# Elecrow_SIMduino_v2_2.net
KiCad netlist of a schematic drawn in EAGLE
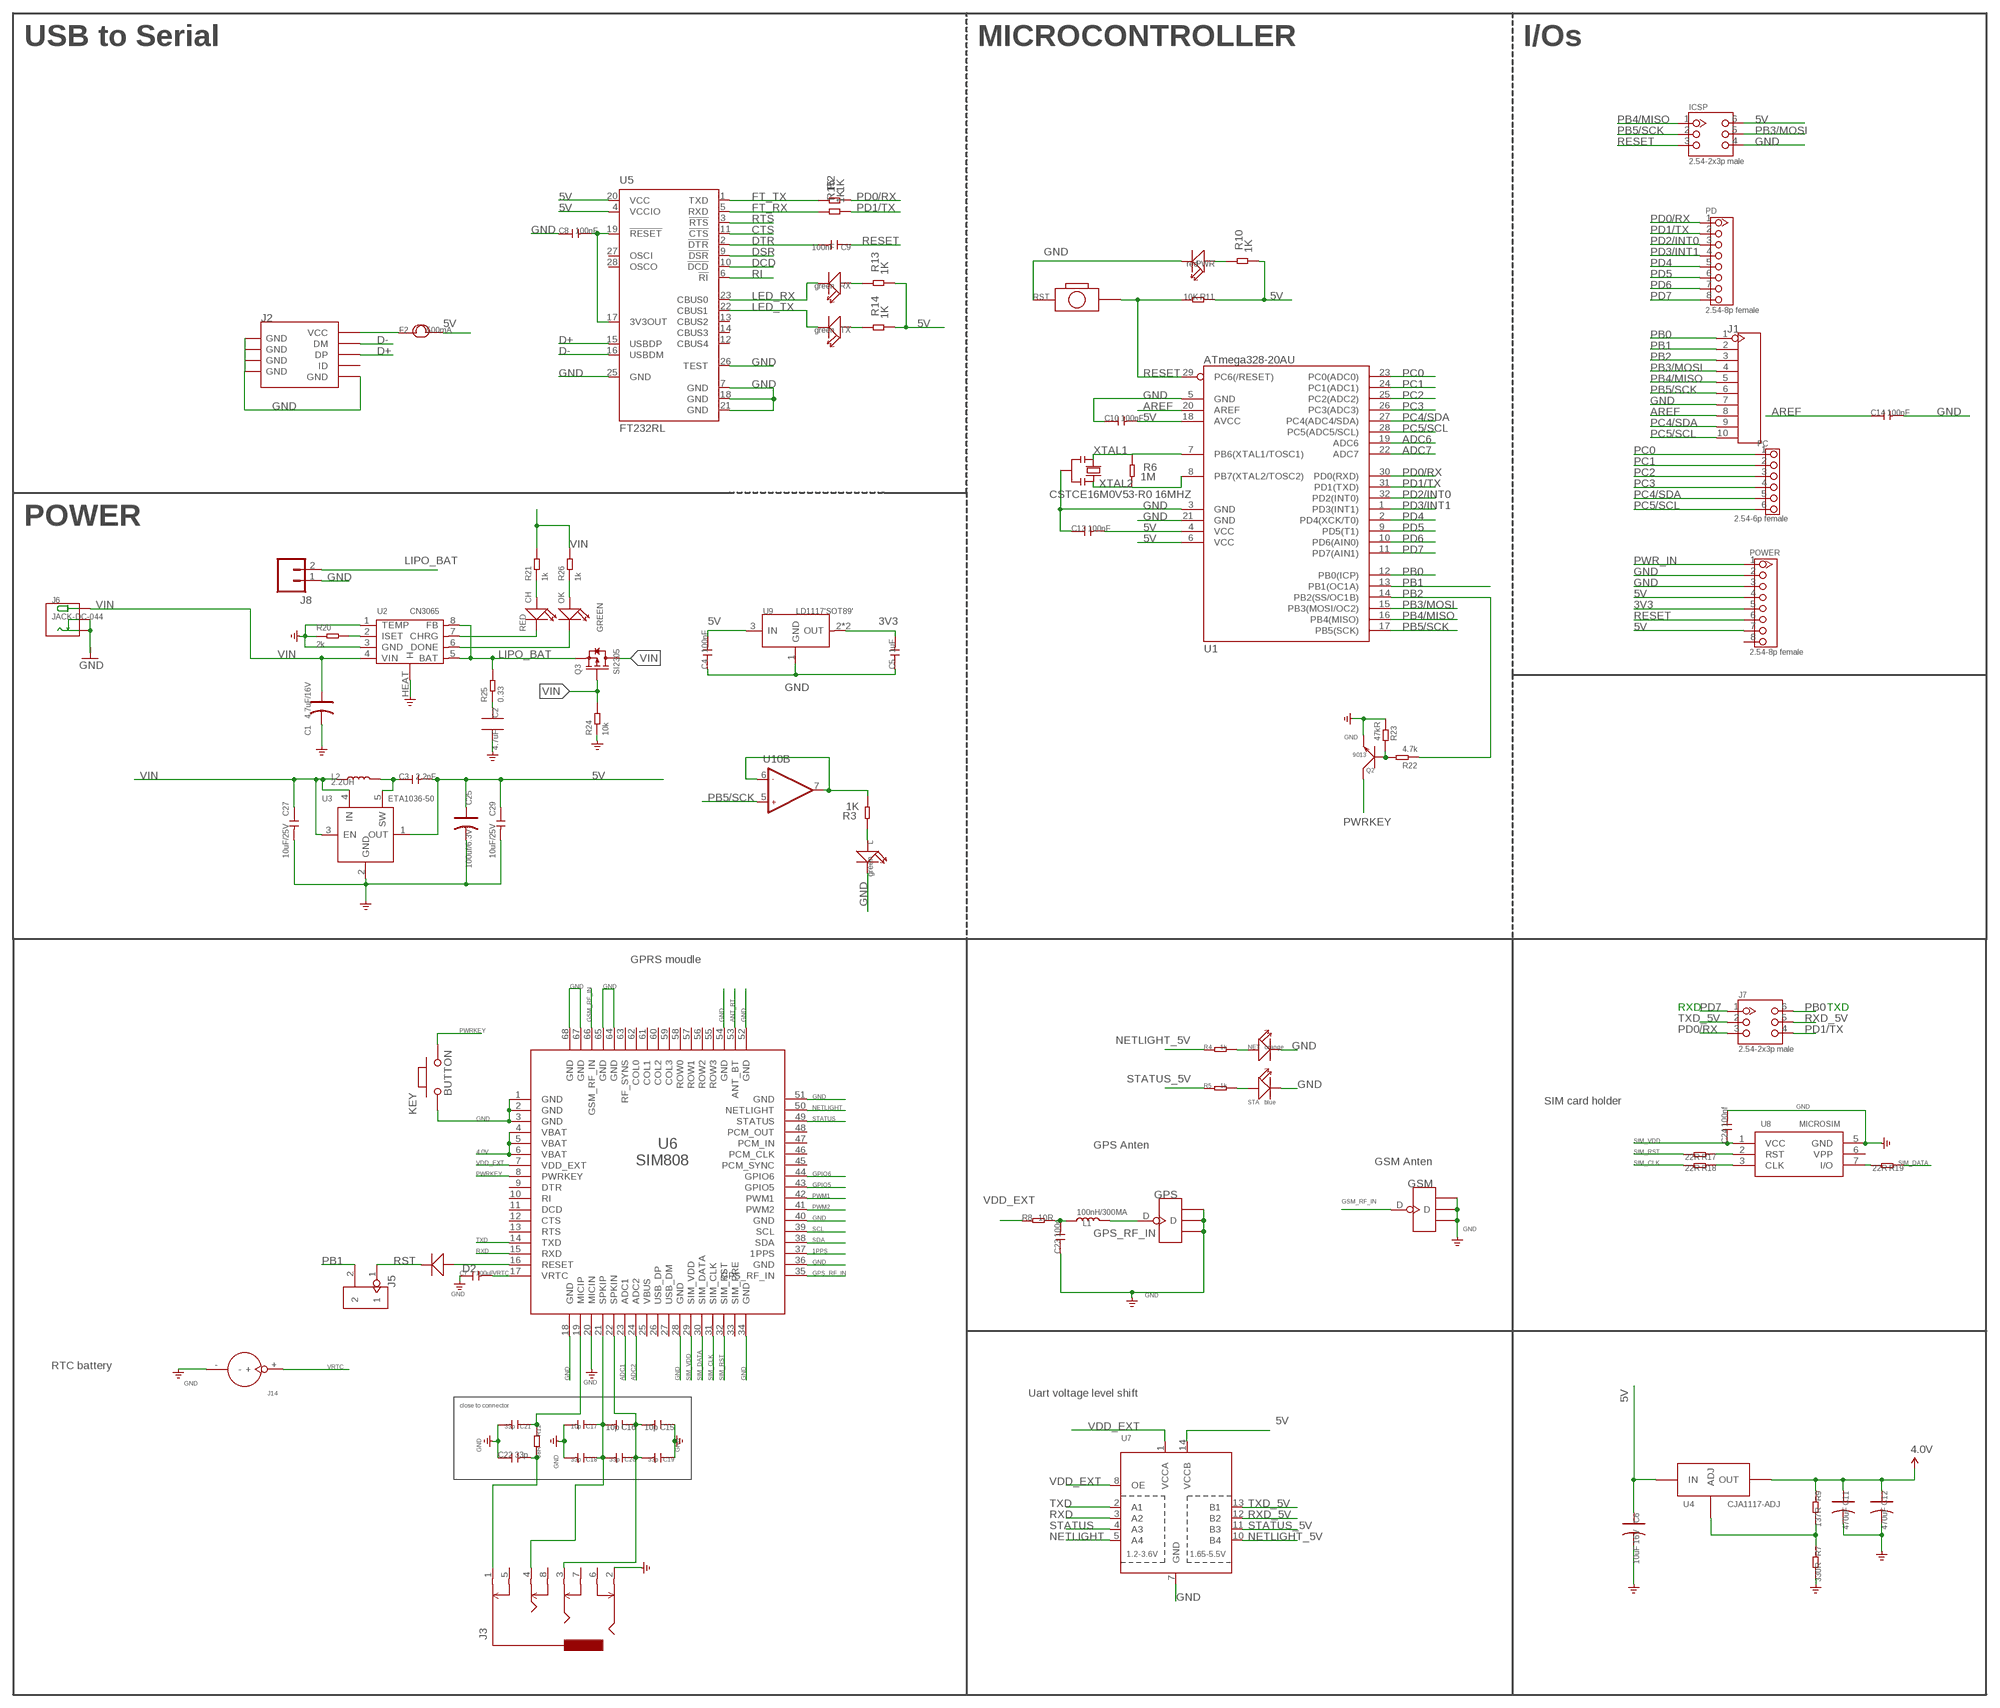
[diagram p0: schematic, sheet 1]

(export (version "E")
  (design (tool "Eeschema 10.0.6"))
  (components
    (comp (ref "C1")
      (value "4.7uF/16V")
      (footprint "eagle-import:AVX_A")
      (libsource (lib "eagle-import") (part "006-CAP_AVX_A"))
    )
    (comp (ref "C2")
      (value "4.7uF")
      (footprint "eagle-import:0805")
      (libsource (lib "eagle-import") (part "C0805"))
    )
    (comp (ref "C3")
      (value "2.2nF")
      (footprint "eagle-import:C0603")
      (libsource (lib "eagle-import") (part "C-0603"))
    )
    (comp (ref "C4")
      (value "100nF")
      (footprint "eagle-import:C0603")
      (libsource (lib "eagle-import") (part "C-0603"))
    )
    (comp (ref "C5")
      (value "1uF")
      (footprint "eagle-import:C0603")
      (libsource (lib "eagle-import") (part "C-0603"))
    )
    (comp (ref "C6")
      (value "10uF 16V")
      (footprint "eagle-import:AVX-A")
      (libsource (lib "eagle-import") (part "CAP-AVX-A"))
    )
    (comp (ref "C7")
      (value "100uF")
      (footprint "eagle-import:C0805")
      (libsource (lib "eagle-import") (part "C-0805"))
    )
    (comp (ref "C8")
      (value "100nF")
      (footprint "eagle-import:C0603")
      (libsource (lib "eagle-import") (part "C-0603"))
    )
    (comp (ref "C9")
      (value "100nF")
      (footprint "eagle-import:C0603")
      (libsource (lib "eagle-import") (part "C-0603"))
    )
    (comp (ref "C10")
      (value "100nF")
      (footprint "eagle-import:C0603")
      (libsource (lib "eagle-import") (part "C-0603"))
    )
    (comp (ref "C11")
      (value "470uF")
      (footprint "eagle-import:AVX-D")
      (libsource (lib "eagle-import") (part "CAP-AVX-D"))
    )
    (comp (ref "C12")
      (value "470uF")
      (footprint "eagle-import:AVX-D")
      (libsource (lib "eagle-import") (part "CAP-AVX-D"))
    )
    (comp (ref "C13")
      (value "100nF")
      (footprint "eagle-import:C0603")
      (libsource (lib "eagle-import") (part "C-0603"))
    )
    (comp (ref "C14")
      (value "100nF")
      (footprint "eagle-import:C0603")
      (libsource (lib "eagle-import") (part "C-0603"))
    )
    (comp (ref "C15")
      (value "10p")
      (footprint "eagle-import:C0402")
      (libsource (lib "eagle-import") (part "C-0402"))
    )
    (comp (ref "C16")
      (value "10p")
      (footprint "eagle-import:C0402")
      (libsource (lib "eagle-import") (part "C-0402"))
    )
    (comp (ref "C17")
      (value "10p")
      (footprint "eagle-import:C0402")
      (libsource (lib "eagle-import") (part "C-0402"))
    )
    (comp (ref "C18")
      (value "33p")
      (footprint "eagle-import:C0402")
      (libsource (lib "eagle-import") (part "C-0402"))
    )
    (comp (ref "C19")
      (value "33p")
      (footprint "eagle-import:C0402")
      (libsource (lib "eagle-import") (part "C-0402"))
    )
    (comp (ref "C20")
      (value "33p")
      (footprint "eagle-import:C0402")
      (libsource (lib "eagle-import") (part "C-0402"))
    )
    (comp (ref "C21")
      (value "33p")
      (footprint "eagle-import:C0603")
      (libsource (lib "eagle-import") (part "C-0603"))
    )
    (comp (ref "C22")
      (value "33p")
      (footprint "eagle-import:C0603")
      (libsource (lib "eagle-import") (part "C-0603"))
    )
    (comp (ref "C23")
      (value "100n")
      (footprint "eagle-import:C0603")
      (libsource (lib "eagle-import") (part "C-0603"))
    )
    (comp (ref "C24")
      (value "100nf")
      (footprint "eagle-import:C0603")
      (libsource (lib "eagle-import") (part "C-0603"))
    )
    (comp (ref "C25")
      (value "100uf/6.3V")
      (footprint "eagle-import:AVX-B")
      (libsource (lib "eagle-import") (part "Discrete_CAP-AVX-B"))
    )
    (comp (ref "C27")
      (value "10uF/25V")
      (footprint "eagle-import:C0805")
      (libsource (lib "eagle-import") (part "CAP-0805"))
    )
    (comp (ref "C29")
      (value "10uF/25V")
      (footprint "eagle-import:C0805")
      (libsource (lib "eagle-import") (part "CAP-0805"))
    )
    (comp (ref "CH")
      (value "RED")
      (footprint "eagle-import:LED-0603")
      (libsource (lib "eagle-import") (part "Discrete-new_LED'0603'"))
    )
    (comp (ref "D2")
      (value "D'0805'")
      (footprint "eagle-import:SOD323")
      (libsource (lib "eagle-import") (part "D'0805'"))
    )
    (comp (ref "F2")
      (value "500mA")
      (footprint "eagle-import:R1206@1")
      (libsource (lib "eagle-import") (part "FUSE1206"))
    )
    (comp (ref "GPS")
      (value "ANTENNA-U-FL")
      (footprint "eagle-import:4P-U-FL")
      (libsource (lib "eagle-import") (part "ANTENNA-U-FL"))
    )
    (comp (ref "GSM")
      (value "ANTENNA-U-FL")
      (footprint "eagle-import:4P-U-FL")
      (libsource (lib "eagle-import") (part "ANTENNA-U-FL"))
    )
    (comp (ref "ICSP")
      (value "2.54-2x3p male")
      (footprint "eagle-import:2X3P-2.54")
      (libsource (lib "eagle-import") (part "HEADER-2X3P-2.54"))
    )
    (comp (ref "J1")
      (value "HEADER-10P-2.54")
      (footprint "eagle-import:10P-2.54")
      (libsource (lib "eagle-import") (part "HEADER-10P-2.54"))
    )
    (comp (ref "J2")
      (value "USB-MINIUSB-5P-STRONG")
      (footprint "eagle-import:MINI-SMD-5P")
      (libsource (lib "eagle-import") (part "USB-MINIUSB-5P-STRONG"))
    )
    (comp (ref "J3")
      (value "AUDIO-8P'PJ-3536-L6S'")
      (footprint "eagle-import:8P-3.5-SMD")
      (libsource (lib "eagle-import") (part "AUDIO-8P'PJ-3536-L6S'"))
    )
    (comp (ref "J5")
      (value "HEADER-2P-65/35MIL")
      (footprint "eagle-import:2P-2.54-65_35MIL")
      (libsource (lib "eagle-import") (part "HEADER-2P-65/35MIL"))
    )
    (comp (ref "J6")
      (value "JACK-DC-044")
      (footprint "eagle-import:DC-404")
      (libsource (lib "eagle-import") (part "JACK-DC-044"))
    )
    (comp (ref "J7")
      (value "2.54-2x3p male")
      (footprint "eagle-import:2X3P-2.54")
      (libsource (lib "eagle-import") (part "HEADER-2X3P-2.54"))
    )
    (comp (ref "J8")
      (value "M02-JST-2MM-SMT")
      (footprint "eagle-import:JST-2-SMD")
      (libsource (lib "eagle-import") (part "M02-JST-2MM-SMT"))
    )
    (comp (ref "J14")
      (value "HOLDER-BATTERY-2P-CR1220")
      (footprint "eagle-import:CR1220")
      (libsource (lib "eagle-import") (part "HOLDER-BATTERY-2P-CR1220"))
    )
    (comp (ref "KEY")
      (value "BUTTON")
      (footprint "eagle-import:157SW")
      (libsource (lib "eagle-import") (part "PB157"))
    )
    (comp (ref "L")
      (value "green")
      (footprint "eagle-import:LED-0603")
      (libsource (lib "eagle-import") (part "LED'0603'"))
    )
    (comp (ref "L1")
      (value "100nH/300MA")
      (footprint "eagle-import:L0603")
      (libsource (lib "eagle-import") (part "L'0603'"))
    )
    (comp (ref "L2")
      (value "2.2UH")
      (footprint "eagle-import:SD32-4R7MC")
      (libsource (lib "eagle-import") (part "CD32'4R7'"))
    )
    (comp (ref "NET")
      (value "orange")
      (footprint "eagle-import:LED-0603")
      (libsource (lib "eagle-import") (part "LED'0603'"))
    )
    (comp (ref "OK")
      (value "GREEN")
      (footprint "eagle-import:LED-0603")
      (libsource (lib "eagle-import") (part "Discrete-new_LED'0603'"))
    )
    (comp (ref "PC")
      (value "2.54-6p female")
      (footprint "eagle-import:6P-2.54-65_35MIL")
      (libsource (lib "eagle-import") (part "HEADER-6P-65/35MIL"))
    )
    (comp (ref "PD")
      (value "2.54-8p female")
      (footprint "eagle-import:8P-2.54")
      (libsource (lib "eagle-import") (part "HEADER-8P-2.54"))
    )
    (comp (ref "POWER")
      (value "2.54-8p female")
      (footprint "eagle-import:8P-2.54")
      (libsource (lib "eagle-import") (part "HEADER-8P-2.54"))
    )
    (comp (ref "PWR")
      (value "red")
      (footprint "eagle-import:LED-0603")
      (libsource (lib "eagle-import") (part "LED'0603'"))
    )
    (comp (ref "Q2")
      (value "9013")
      (footprint "eagle-import:SOT23")
      (libsource (lib "eagle-import") (part "TRANSISTOR-NPN-SOT23"))
    )
    (comp (ref "Q3")
      (value "SI2305")
      (footprint "eagle-import:SOT-23")
      (libsource (lib "eagle-import") (part "MOSFET-P'SI2323CDS/SI2305DS{lt}BR{gt}'"))
    )
    (comp (ref "R2")
      (value "1K")
      (footprint "eagle-import:R0603")
      (libsource (lib "eagle-import") (part "R-0603"))
    )
    (comp (ref "R3")
      (value "1K")
      (footprint "eagle-import:R0603")
      (libsource (lib "eagle-import") (part "R-0603"))
    )
    (comp (ref "R4")
      (value "1k")
      (footprint "eagle-import:R0603")
      (libsource (lib "eagle-import") (part "R-0603"))
    )
    (comp (ref "R5")
      (value "1k")
      (footprint "eagle-import:R0603")
      (libsource (lib "eagle-import") (part "R-0603"))
    )
    (comp (ref "R6")
      (value "1M")
      (footprint "eagle-import:R0603")
      (libsource (lib "eagle-import") (part "R-0603"))
    )
    (comp (ref "R7")
      (value "330R")
      (footprint "eagle-import:R0603")
      (libsource (lib "eagle-import") (part "R-0603"))
    )
    (comp (ref "R8")
      (value "10R")
      (footprint "eagle-import:R0603")
      (libsource (lib "eagle-import") (part "R-0603"))
    )
    (comp (ref "R9")
      (value "137R")
      (footprint "eagle-import:R0603")
      (libsource (lib "eagle-import") (part "R-0603"))
    )
    (comp (ref "R10")
      (value "1K")
      (footprint "eagle-import:R0603")
      (libsource (lib "eagle-import") (part "R-0603"))
    )
    (comp (ref "R11")
      (value "10K")
      (footprint "eagle-import:R0603")
      (libsource (lib "eagle-import") (part "R-0603"))
    )
    (comp (ref "R12")
      (value "68R")
      (footprint "eagle-import:R0603")
      (libsource (lib "eagle-import") (part "R-0603"))
    )
    (comp (ref "R13")
      (value "1K")
      (footprint "eagle-import:R0603")
      (libsource (lib "eagle-import") (part "R-0603"))
    )
    (comp (ref "R14")
      (value "1K")
      (footprint "eagle-import:R0603")
      (libsource (lib "eagle-import") (part "R-0603"))
    )
    (comp (ref "R15")
      (value "1K")
      (footprint "eagle-import:R0603")
      (libsource (lib "eagle-import") (part "R-0603"))
    )
    (comp (ref "R17")
      (value "22R")
      (footprint "eagle-import:R0603")
      (libsource (lib "eagle-import") (part "R-0603"))
    )
    (comp (ref "R18")
      (value "22R")
      (footprint "eagle-import:R0603")
      (libsource (lib "eagle-import") (part "R-0603"))
    )
    (comp (ref "R19")
      (value "22R")
      (footprint "eagle-import:R0603")
      (libsource (lib "eagle-import") (part "R-0603"))
    )
    (comp (ref "R20")
      (value "2k")
      (footprint "eagle-import:R0603")
      (libsource (lib "eagle-import") (part "RES-0603"))
    )
    (comp (ref "R21")
      (value "1k")
      (footprint "eagle-import:R0603")
      (libsource (lib "eagle-import") (part "RES-0603"))
    )
    (comp (ref "R22")
      (value "4.7k")
      (footprint "eagle-import:R0402")
      (libsource (lib "eagle-import") (part "R-0402"))
    )
    (comp (ref "R23")
      (value "47kR")
      (footprint "eagle-import:R0402")
      (libsource (lib "eagle-import") (part "R-0402"))
    )
    (comp (ref "R24")
      (value "10k")
      (footprint "eagle-import:R0603")
      (libsource (lib "eagle-import") (part "RES-0603"))
    )
    (comp (ref "R25")
      (value "0.33")
      (footprint "eagle-import:R0603")
      (libsource (lib "eagle-import") (part "RES-0603"))
    )
    (comp (ref "R26")
      (value "1k")
      (footprint "eagle-import:R0603")
      (libsource (lib "eagle-import") (part "RES-0603"))
    )
    (comp (ref "RST")
      (value "BOTTON-2P-90D")
      (footprint "eagle-import:2P-7.62X3.56-90D")
      (libsource (lib "eagle-import") (part "BOTTON-2P-90D"))
    )
    (comp (ref "RX")
      (value "green")
      (footprint "eagle-import:LED-0603")
      (libsource (lib "eagle-import") (part "LED'0603'"))
    )
    (comp (ref "STA")
      (value "blue")
      (footprint "eagle-import:LED-0603")
      (libsource (lib "eagle-import") (part "LED'0603'"))
    )
    (comp (ref "TX")
      (value "green")
      (footprint "eagle-import:LED-0603")
      (libsource (lib "eagle-import") (part "LED'0603'"))
    )
    (comp (ref "U1")
      (value "ATmega328-20AU")
      (footprint "eagle-import:TQFP32")
      (libsource (lib "eagle-import") (part "ATMEGA168"))
    )
    (comp (ref "U2")
      (value "CN3065")
      (footprint "eagle-import:DFN-8")
      (libsource (lib "eagle-import") (part "PMIC-CN3065-DFN8"))
    )
    (comp (ref "U3")
      (value "ETA1036-50")
      (footprint "eagle-import:SOT23-5")
      (libsource (lib "eagle-import") (part "ETA1036"))
    )
    (comp (ref "U4")
      (value "CJA1117-ADJ")
      (footprint "eagle-import:SOT89")
      (libsource (lib "eagle-import") (part "CJA1117-ADJ"))
    )
    (comp (ref "U5")
      (value "FT232RL")
      (footprint "eagle-import:SSOP28")
      (libsource (lib "eagle-import") (part "FT232RL"))
    )
    (comp (ref "U6")
      (value "SIM808")
      (footprint "eagle-import:SIM808")
      (libsource (lib "eagle-import") (part "SIM808"))
    )
    (comp (ref "U7")
      (value "TXB0104PWR")
      (footprint "eagle-import:TSSOP14")
      (libsource (lib "eagle-import") (part "TXB0104PWR"))
    )
    (comp (ref "U8")
      (value "MICROSIM")
      (footprint "eagle-import:MICROSIM")
      (libsource (lib "eagle-import") (part "MICROSIM"))
    )
    (comp (ref "U9")
      (value "LD1117'SOT89'")
      (footprint "eagle-import:SOT89")
      (libsource (lib "eagle-import") (part "LD1117'SOT89'"))
    )
    (comp (ref "U10")
      (value "LMV358DGK")
      (footprint "eagle-import:MSOP8")
      (libsource (lib "eagle-import") (part "LMV358DGK"))
    )
    (comp (ref "Y2")
      (value "CSTCE16M0V53-R0 16MHZ")
      (footprint "eagle-import:RESONATOR")
      (libsource (lib "eagle-import") (part "RESONATORMU"))
    )
  )
  (nets
    (net (code "1") (name "/1PPS") (class "Default")
      (node (ref "U6") (pin "37") (pinfunction "1PPS_37") (pintype "input"))
    )
    (net (code "2") (name "/3V3") (class "Default")
      (node (ref "C5") (pin "2") (pinfunction "2_2") (pintype "passive"))
      (node (ref "POWER") (pin "5") (pinfunction "5_5") (pintype "bidirectional"))
      (node (ref "U9") (pin "2") (pinfunction "OUT_2") (pintype "bidirectional"))
      (node (ref "U9") (pin "4") (pinfunction "OUT_4") (pintype "bidirectional"))
    )
    (net (code "3") (name "/5V") (class "Default")
      (node (ref "C10") (pin "2") (pinfunction "2_2") (pintype "passive"))
      (node (ref "C13") (pin "2") (pinfunction "2_2") (pintype "passive"))
      (node (ref "C25") (pin "+") (pinfunction "+_+") (pintype "passive"))
      (node (ref "C29") (pin "1") (pinfunction "1_1") (pintype "passive"))
      (node (ref "C3") (pin "2") (pinfunction "2_2") (pintype "passive"))
      (node (ref "C4") (pin "2") (pinfunction "2_2") (pintype "passive"))
      (node (ref "C6") (pin "+") (pinfunction "+_+") (pintype "passive"))
      (node (ref "F2") (pin "2") (pinfunction "2_2") (pintype "bidirectional"))
      (node (ref "ICSP") (pin "6") (pinfunction "6_6") (pintype "bidirectional"))
      (node (ref "POWER") (pin "4") (pinfunction "4_4") (pintype "bidirectional"))
      (node (ref "POWER") (pin "7") (pinfunction "7_7") (pintype "bidirectional"))
      (node (ref "R10") (pin "1") (pinfunction "1_1") (pintype "passive"))
      (node (ref "R11") (pin "1") (pinfunction "1_1") (pintype "passive"))
      (node (ref "R13") (pin "1") (pinfunction "1_1") (pintype "passive"))
      (node (ref "R14") (pin "1") (pinfunction "1_1") (pintype "passive"))
      (node (ref "U1") (pin "18") (pinfunction "AVCC_18") (pintype "bidirectional"))
      (node (ref "U1") (pin "4") (pinfunction "VCC_4") (pintype "bidirectional"))
      (node (ref "U1") (pin "6") (pinfunction "VCC_6") (pintype "bidirectional"))
      (node (ref "U3") (pin "1") (pinfunction "OUT_1") (pintype "bidirectional"))
      (node (ref "U4") (pin "3") (pinfunction "IN_3") (pintype "bidirectional"))
      (node (ref "U5") (pin "20") (pinfunction "VCC_20") (pintype "input"))
      (node (ref "U5") (pin "4") (pinfunction "VCCIO_4") (pintype "input"))
      (node (ref "U7") (pin "14") (pinfunction "VCCB_14") (pintype "bidirectional"))
      (node (ref "U9") (pin "3") (pinfunction "IN_3") (pintype "bidirectional"))
    )
    (net (code "4") (name "/ADC1") (class "Default")
      (node (ref "U6") (pin "23") (pinfunction "ADC1_23") (pintype "input"))
    )
    (net (code "5") (name "/ADC2") (class "Default")
      (node (ref "U6") (pin "24") (pinfunction "ADC2_24") (pintype "input"))
    )
    (net (code "6") (name "/ADC6") (class "Default")
      (node (ref "U1") (pin "19") (pinfunction "ADC6_19") (pintype "bidirectional"))
    )
    (net (code "7") (name "/ADC7") (class "Default")
      (node (ref "U1") (pin "22") (pinfunction "ADC7_22") (pintype "bidirectional"))
    )
    (net (code "8") (name "/ANT_BT") (class "Default")
      (node (ref "U6") (pin "53") (pinfunction "ANT_BT_53") (pintype "power_in"))
    )
    (net (code "9") (name "/AREF") (class "Default")
      (node (ref "C14") (pin "1") (pinfunction "1_1") (pintype "passive"))
      (node (ref "J1") (pin "8") (pinfunction "8_8") (pintype "bidirectional"))
      (node (ref "U1") (pin "20") (pinfunction "AREF_20") (pintype "bidirectional"))
    )
    (net (code "10") (name "/COL0") (class "Default")
      (node (ref "U6") (pin "62") (pinfunction "COL0_62") (pintype "power_in"))
    )
    (net (code "11") (name "/COL1") (class "Default")
      (node (ref "U6") (pin "61") (pinfunction "COL1_61") (pintype "power_in"))
    )
    (net (code "12") (name "/COL2") (class "Default")
      (node (ref "U6") (pin "60") (pinfunction "COL2_60") (pintype "power_in"))
    )
    (net (code "13") (name "/COL3") (class "Default")
      (node (ref "U6") (pin "59") (pinfunction "COL3_59") (pintype "power_in"))
    )
    (net (code "14") (name "/CTS") (class "Default")
      (node (ref "U5") (pin "11") (pinfunction "~{CTS}_11") (pintype "input"))
    )
    (net (code "15") (name "/D+") (class "Default")
      (node (ref "J2") (pin "3") (pinfunction "DP_3") (pintype "bidirectional"))
      (node (ref "U5") (pin "15") (pinfunction "USBDP_15") (pintype "input"))
    )
    (net (code "16") (name "/D-") (class "Default")
      (node (ref "J2") (pin "2") (pinfunction "DM_2") (pintype "bidirectional"))
      (node (ref "U5") (pin "16") (pinfunction "USBDM_16") (pintype "input"))
    )
    (net (code "17") (name "/DCD") (class "Default")
      (node (ref "U5") (pin "10") (pinfunction "~{DCD}_10") (pintype "input"))
    )
    (net (code "18") (name "/DSR") (class "Default")
      (node (ref "U5") (pin "9") (pinfunction "~{DSR}_9") (pintype "input"))
    )
    (net (code "19") (name "/DTR") (class "Default")
      (node (ref "C9") (pin "2") (pinfunction "2_2") (pintype "passive"))
      (node (ref "U5") (pin "2") (pinfunction "~{DTR}_2") (pintype "input"))
    )
    (net (code "20") (name "/FT_RX") (class "Default")
      (node (ref "R15") (pin "2") (pinfunction "2_2") (pintype "passive"))
      (node (ref "U5") (pin "5") (pinfunction "RXD_5") (pintype "input"))
    )
    (net (code "21") (name "/FT_TX") (class "Default")
      (node (ref "R2") (pin "2") (pinfunction "2_2") (pintype "passive"))
      (node (ref "U5") (pin "1") (pinfunction "TXD_1") (pintype "input"))
    )
    (net (code "22") (name "/GPIO5") (class "Default")
      (node (ref "U6") (pin "43") (pinfunction "GPIO5_43") (pintype "output"))
    )
    (net (code "23") (name "/GPIO6") (class "Default")
      (node (ref "U6") (pin "44") (pinfunction "GPIO6_44") (pintype "output"))
    )
    (net (code "24") (name "/GPS_RF_IN") (class "Default")
      (node (ref "GPS") (pin "D") (pinfunction "D_D") (pintype "bidirectional"))
      (node (ref "L1") (pin "2") (pinfunction "2_2") (pintype "passive"))
      (node (ref "U6") (pin "35") (pinfunction "GPS_RF_IN_35") (pintype "output"))
    )
    (net (code "25") (name "/GSM_RF_IN") (class "Default")
      (node (ref "GSM") (pin "D") (pinfunction "D_D") (pintype "bidirectional"))
      (node (ref "U6") (pin "66") (pinfunction "GSM_RF_IN_66") (pintype "power_in"))
    )
    (net (code "26") (name "/LED_RX") (class "Default")
      (node (ref "RX") (pin "-") (pinfunction "-_-") (pintype "passive"))
      (node (ref "U5") (pin "23") (pinfunction "CBUS0_23") (pintype "input"))
    )
    (net (code "27") (name "/LED_TX") (class "Default")
      (node (ref "TX") (pin "-") (pinfunction "-_-") (pintype "passive"))
      (node (ref "U5") (pin "22") (pinfunction "CBUS1_22") (pintype "input"))
    )
    (net (code "28") (name "/LIPO_BAT") (class "Default")
      (node (ref "J8") (pin "2") (pinfunction "2_2") (pintype "passive"))
      (node (ref "Q3") (pin "2") (pinfunction "S_2") (pintype "passive"))
      (node (ref "R25") (pin "2") (pinfunction "2_2") (pintype "passive"))
      (node (ref "U2") (pin "5") (pinfunction "BAT_5") (pintype "bidirectional"))
      (node (ref "U2") (pin "8") (pinfunction "FB_8") (pintype "input"))
    )
    (net (code "29") (name "/NETLIGHT") (class "Default")
      (node (ref "U6") (pin "50") (pinfunction "NETLIGHT_50") (pintype "output"))
      (node (ref "U7") (pin "5") (pinfunction "A4_5") (pintype "bidirectional"))
    )
    (net (code "30") (name "/NETLIGHT_5V") (class "Default")
      (node (ref "R4") (pin "1") (pinfunction "1_1") (pintype "passive"))
      (node (ref "U7") (pin "10") (pinfunction "B4_10") (pintype "bidirectional"))
    )
    (net (code "31") (name "/PB0") (class "Default")
      (node (ref "J1") (pin "1") (pinfunction "1_1") (pintype "bidirectional"))
      (node (ref "J7") (pin "6") (pinfunction "6_6") (pintype "bidirectional"))
      (node (ref "U1") (pin "12") (pinfunction "PB0(ICP)_12") (pintype "bidirectional"))
    )
    (net (code "32") (name "/PB1") (class "Default")
      (node (ref "J1") (pin "2") (pinfunction "2_2") (pintype "bidirectional"))
      (node (ref "J5") (pin "2") (pinfunction "2_2") (pintype "bidirectional"))
      (node (ref "U1") (pin "13") (pinfunction "PB1(OC1A)_13") (pintype "bidirectional"))
    )
    (net (code "33") (name "/PB2") (class "Default")
      (node (ref "J1") (pin "3") (pinfunction "3_3") (pintype "bidirectional"))
      (node (ref "R22") (pin "1") (pinfunction "1_1") (pintype "passive"))
      (node (ref "U1") (pin "14") (pinfunction "PB2(SS/OC1B)_14") (pintype "bidirectional"))
    )
    (net (code "34") (name "/PB3{slash}MOSI") (class "Default")
      (node (ref "ICSP") (pin "5") (pinfunction "5_5") (pintype "bidirectional"))
      (node (ref "J1") (pin "4") (pinfunction "4_4") (pintype "bidirectional"))
      (node (ref "U1") (pin "15") (pinfunction "PB3(MOSI/OC2)_15") (pintype "bidirectional"))
    )
    (net (code "35") (name "/PB4{slash}MISO") (class "Default")
      (node (ref "ICSP") (pin "1") (pinfunction "1_1") (pintype "bidirectional"))
      (node (ref "J1") (pin "5") (pinfunction "5_5") (pintype "bidirectional"))
      (node (ref "U1") (pin "16") (pinfunction "PB4(MISO)_16") (pintype "bidirectional"))
    )
    (net (code "36") (name "/PB5{slash}SCK") (class "Default")
      (node (ref "ICSP") (pin "2") (pinfunction "2_2") (pintype "bidirectional"))
      (node (ref "J1") (pin "6") (pinfunction "6_6") (pintype "bidirectional"))
      (node (ref "U1") (pin "17") (pinfunction "PB5(SCK)_17") (pintype "bidirectional"))
      (node (ref "U10") (pin "5") (pinfunction "+IN2_5") (pintype "input"))
    )
    (net (code "37") (name "/PC0") (class "Default")
      (node (ref "PC") (pin "1") (pinfunction "1_1") (pintype "bidirectional"))
      (node (ref "U1") (pin "23") (pinfunction "PC0(ADC0)_23") (pintype "bidirectional"))
    )
    (net (code "38") (name "/PC1") (class "Default")
      (node (ref "PC") (pin "2") (pinfunction "2_2") (pintype "bidirectional"))
      (node (ref "U1") (pin "24") (pinfunction "PC1(ADC1)_24") (pintype "bidirectional"))
    )
    (net (code "39") (name "/PC2") (class "Default")
      (node (ref "PC") (pin "3") (pinfunction "3_3") (pintype "bidirectional"))
      (node (ref "U1") (pin "25") (pinfunction "PC2(ADC2)_25") (pintype "bidirectional"))
    )
    (net (code "40") (name "/PC3") (class "Default")
      (node (ref "PC") (pin "4") (pinfunction "4_4") (pintype "bidirectional"))
      (node (ref "U1") (pin "26") (pinfunction "PC3(ADC3)_26") (pintype "bidirectional"))
    )
    (net (code "41") (name "/PC4{slash}SDA") (class "Default")
      (node (ref "J1") (pin "9") (pinfunction "9_9") (pintype "bidirectional"))
      (node (ref "PC") (pin "5") (pinfunction "5_5") (pintype "bidirectional"))
      (node (ref "U1") (pin "27") (pinfunction "PC4(ADC4/SDA)_27") (pintype "bidirectional"))
    )
    (net (code "42") (name "/PC5{slash}SCL") (class "Default")
      (node (ref "J1") (pin "10") (pinfunction "10_10") (pintype "bidirectional"))
      (node (ref "PC") (pin "6") (pinfunction "6_6") (pintype "bidirectional"))
      (node (ref "U1") (pin "28") (pinfunction "PC5(ADC5/SCL)_28") (pintype "bidirectional"))
    )
    (net (code "43") (name "/PD0{slash}RX") (class "Default")
      (node (ref "J7") (pin "3") (pinfunction "3_3") (pintype "bidirectional"))
      (node (ref "PD") (pin "1") (pinfunction "1_1") (pintype "bidirectional"))
      (node (ref "R2") (pin "1") (pinfunction "1_1") (pintype "passive"))
      (node (ref "U1") (pin "30") (pinfunction "PD0(RXD)_30") (pintype "bidirectional"))
    )
    (net (code "44") (name "/PD1{slash}TX") (class "Default")
      (node (ref "J7") (pin "4") (pinfunction "4_4") (pintype "bidirectional"))
      (node (ref "PD") (pin "2") (pinfunction "2_2") (pintype "bidirectional"))
      (node (ref "R15") (pin "1") (pinfunction "1_1") (pintype "passive"))
      (node (ref "U1") (pin "31") (pinfunction "PD1(TXD)_31") (pintype "bidirectional"))
    )
    (net (code "45") (name "/PD2{slash}INT0") (class "Default")
      (node (ref "PD") (pin "3") (pinfunction "3_3") (pintype "bidirectional"))
      (node (ref "U1") (pin "32") (pinfunction "PD2(INT0)_32") (pintype "bidirectional"))
    )
    (net (code "46") (name "/PD3{slash}INT1") (class "Default")
      (node (ref "PD") (pin "4") (pinfunction "4_4") (pintype "bidirectional"))
      (node (ref "U1") (pin "1") (pinfunction "PD3(INT1)_1") (pintype "bidirectional"))
    )
    (net (code "47") (name "/PD4") (class "Default")
      (node (ref "PD") (pin "5") (pinfunction "5_5") (pintype "bidirectional"))
      (node (ref "U1") (pin "2") (pinfunction "PD4(XCK/T0)_2") (pintype "bidirectional"))
    )
    (net (code "48") (name "/PD5") (class "Default")
      (node (ref "PD") (pin "6") (pinfunction "6_6") (pintype "bidirectional"))
      (node (ref "U1") (pin "9") (pinfunction "PD5(T1)_9") (pintype "bidirectional"))
    )
    (net (code "49") (name "/PD6") (class "Default")
      (node (ref "PD") (pin "7") (pinfunction "7_7") (pintype "bidirectional"))
      (node (ref "U1") (pin "10") (pinfunction "PD6(AIN0)_10") (pintype "bidirectional"))
    )
    (net (code "50") (name "/PD7") (class "Default")
      (node (ref "J7") (pin "1") (pinfunction "1_1") (pintype "bidirectional"))
      (node (ref "PD") (pin "8") (pinfunction "8_8") (pintype "bidirectional"))
      (node (ref "U1") (pin "11") (pinfunction "PD7(AIN1)_11") (pintype "bidirectional"))
    )
    (net (code "51") (name "/PWM1") (class "Default")
      (node (ref "U6") (pin "42") (pinfunction "PWM1_42") (pintype "output"))
    )
    (net (code "52") (name "/PWM2") (class "Default")
      (node (ref "U6") (pin "41") (pinfunction "PWM2_41") (pintype "output"))
    )
    (net (code "53") (name "/PWRKEY") (class "Default")
      (node (ref "KEY") (pin "2") (pinfunction "2_2") (pintype "passive"))
      (node (ref "Q2") (pin "3") (pinfunction "C_3") (pintype "passive"))
      (node (ref "U6") (pin "8") (pinfunction "PWRKEY_8") (pintype "input"))
    )
    (net (code "54") (name "/PWR_IN") (class "Default")
      (node (ref "POWER") (pin "1") (pinfunction "1_1") (pintype "bidirectional"))
    )
    (net (code "55") (name "/RESET") (class "Default")
      (node (ref "C9") (pin "1") (pinfunction "1_1") (pintype "passive"))
      (node (ref "ICSP") (pin "3") (pinfunction "3_3") (pintype "bidirectional"))
      (node (ref "POWER") (pin "6") (pinfunction "6_6") (pintype "bidirectional"))
      (node (ref "R11") (pin "2") (pinfunction "2_2") (pintype "passive"))
      (node (ref "RST") (pin "P$2") (pinfunction "2_P$2") (pintype "bidirectional"))
      (node (ref "U1") (pin "29") (pinfunction "PC6(/RESET)_29") (pintype "bidirectional"))
    )
    (net (code "56") (name "/RF_SYNS") (class "Default")
      (node (ref "U6") (pin "63") (pinfunction "RF_SYNS_63") (pintype "power_in"))
    )
    (net (code "57") (name "/RI") (class "Default")
      (node (ref "U5") (pin "6") (pinfunction "~{RI}_6") (pintype "input"))
    )
    (net (code "58") (name "/ROW0") (class "Default")
      (node (ref "U6") (pin "58") (pinfunction "ROW0_58") (pintype "power_in"))
    )
    (net (code "59") (name "/ROW1") (class "Default")
      (node (ref "U6") (pin "57") (pinfunction "ROW1_57") (pintype "power_in"))
    )
    (net (code "60") (name "/ROW2") (class "Default")
      (node (ref "U6") (pin "56") (pinfunction "ROW2_56") (pintype "power_in"))
    )
    (net (code "61") (name "/ROW3") (class "Default")
      (node (ref "U6") (pin "55") (pinfunction "ROW3_55") (pintype "power_in"))
    )
    (net (code "62") (name "/RST") (class "Default")
      (node (ref "D2") (pin "-") (pinfunction "-_-") (pintype "passive"))
      (node (ref "J5") (pin "1") (pinfunction "1_1") (pintype "bidirectional"))
    )
    (net (code "63") (name "/RTS") (class "Default")
      (node (ref "U5") (pin "3") (pinfunction "~{RTS}_3") (pintype "input"))
    )
    (net (code "64") (name "/RXD") (class "Default")
      (node (ref "U6") (pin "15") (pinfunction "RXD_15") (pintype "input"))
      (node (ref "U7") (pin "3") (pinfunction "A2_3") (pintype "bidirectional"))
    )
    (net (code "65") (name "/RXD_5V") (class "Default")
      (node (ref "J7") (pin "5") (pinfunction "5_5") (pintype "bidirectional"))
      (node (ref "U7") (pin "12") (pinfunction "B2_12") (pintype "bidirectional"))
    )
    (net (code "66") (name "/SCL") (class "Default")
      (node (ref "U6") (pin "39") (pinfunction "SCL_39") (pintype "output"))
    )
    (net (code "67") (name "/SDA") (class "Default")
      (node (ref "U6") (pin "38") (pinfunction "SDA_38") (pintype "bidirectional"))
    )
    (net (code "68") (name "/SIM_CLK") (class "Default")
      (node (ref "R18") (pin "2") (pinfunction "2_2") (pintype "passive"))
      (node (ref "U6") (pin "31") (pinfunction "SIM_CLK_31") (pintype "output"))
    )
    (net (code "69") (name "/SIM_DATA") (class "Default")
      (node (ref "R19") (pin "1") (pinfunction "1_1") (pintype "passive"))
      (node (ref "U6") (pin "30") (pinfunction "SIM_DATA_30") (pintype "bidirectional"))
    )
    (net (code "70") (name "/SIM_RST") (class "Default")
      (node (ref "R17") (pin "2") (pinfunction "2_2") (pintype "passive"))
      (node (ref "U6") (pin "32") (pinfunction "SIM_RST_32") (pintype "output"))
    )
    (net (code "71") (name "/SIM_VDD") (class "Default")
      (node (ref "C24") (pin "1") (pinfunction "1_1") (pintype "passive"))
      (node (ref "U6") (pin "29") (pinfunction "SIM_VDD_29") (pintype "output"))
      (node (ref "U8") (pin "1") (pinfunction "VCC_1") (pintype "bidirectional"))
    )
    (net (code "72") (name "/STATUS") (class "Default")
      (node (ref "U6") (pin "49") (pinfunction "STATUS_49") (pintype "output"))
      (node (ref "U7") (pin "4") (pinfunction "A3_4") (pintype "bidirectional"))
    )
    (net (code "73") (name "/STATUS_5V") (class "Default")
      (node (ref "R5") (pin "1") (pinfunction "1_1") (pintype "passive"))
      (node (ref "U7") (pin "11") (pinfunction "B3_11") (pintype "bidirectional"))
    )
    (net (code "74") (name "/TXD") (class "Default")
      (node (ref "U6") (pin "14") (pinfunction "TXD_14") (pintype "output"))
      (node (ref "U7") (pin "2") (pinfunction "A1_2") (pintype "bidirectional"))
    )
    (net (code "75") (name "/TXD_5V") (class "Default")
      (node (ref "J7") (pin "2") (pinfunction "2_2") (pintype "bidirectional"))
      (node (ref "U7") (pin "13") (pinfunction "B1_13") (pintype "bidirectional"))
    )
    (net (code "76") (name "/VDD_EXT") (class "Default")
      (node (ref "R8") (pin "1") (pinfunction "1_1") (pintype "passive"))
      (node (ref "U6") (pin "7") (pinfunction "VDD_EXT_7") (pintype "output"))
      (node (ref "U7") (pin "1") (pinfunction "VCCA_1") (pintype "bidirectional"))
      (node (ref "U7") (pin "8") (pinfunction "OE_8") (pintype "bidirectional"))
    )
    (net (code "77") (name "/VRTC") (class "Default")
      (node (ref "C7") (pin "2") (pinfunction "2_2") (pintype "passive"))
      (node (ref "J14") (pin "+") (pinfunction "+_+") (pintype "bidirectional"))
      (node (ref "U6") (pin "17") (pinfunction "VRTC_17") (pintype "bidirectional"))
    )
    (net (code "78") (name "/XTAL1") (class "Default")
      (node (ref "R6") (pin "2") (pinfunction "2_2") (pintype "passive"))
      (node (ref "U1") (pin "7") (pinfunction "PB6(XTAL1/TOSC1)_7") (pintype "bidirectional"))
      (node (ref "Y2") (pin "1") (pinfunction "1_1") (pintype "passive"))
    )
    (net (code "79") (name "/XTAL2") (class "Default")
      (node (ref "R6") (pin "1") (pinfunction "1_1") (pintype "passive"))
      (node (ref "U1") (pin "8") (pinfunction "PB7(XTAL2/TOSC2)_8") (pintype "bidirectional"))
      (node (ref "Y2") (pin "3") (pinfunction "3_3") (pintype "passive"))
    )
    (net (code "80") (name "4.0V") (class "Default")
      (node (ref "C11") (pin "+") (pinfunction "+_+") (pintype "passive"))
      (node (ref "C12") (pin "+") (pinfunction "+_+") (pintype "passive"))
      (node (ref "R9") (pin "1") (pinfunction "1_1") (pintype "passive"))
      (node (ref "U4") (pin "2") (pinfunction "OUT_2") (pintype "bidirectional"))
      (node (ref "U4") (pin "4") (pinfunction "OUT_4") (pintype "bidirectional"))
      (node (ref "U6") (pin "4") (pinfunction "VBAT_4") (pintype "output"))
      (node (ref "U6") (pin "5") (pinfunction "VBAT_5") (pintype "output"))
      (node (ref "U6") (pin "6") (pinfunction "VBAT_6") (pintype "output"))
    )
    (net (code "81") (name "GND") (class "Default")
      (node (ref "C1") (pin "-") (pinfunction "-_-") (pintype "passive"))
      (node (ref "C10") (pin "1") (pinfunction "1_1") (pintype "passive"))
      (node (ref "C11") (pin "-") (pinfunction "-_-") (pintype "passive"))
      (node (ref "C12") (pin "-") (pinfunction "-_-") (pintype "passive"))
      (node (ref "C13") (pin "1") (pinfunction "1_1") (pintype "passive"))
      (node (ref "C14") (pin "2") (pinfunction "2_2") (pintype "passive"))
      (node (ref "C15") (pin "1") (pinfunction "1_1") (pintype "passive"))
      (node (ref "C17") (pin "2") (pinfunction "2_2") (pintype "passive"))
      (node (ref "C18") (pin "2") (pinfunction "2_2") (pintype "passive"))
      (node (ref "C19") (pin "1") (pinfunction "1_1") (pintype "passive"))
      (node (ref "C2") (pin "2") (pinfunction "2_2") (pintype "bidirectional"))
      (node (ref "C21") (pin "2") (pinfunction "2_2") (pintype "passive"))
      (node (ref "C22") (pin "1") (pinfunction "1_1") (pintype "passive"))
      (node (ref "C23") (pin "1") (pinfunction "1_1") (pintype "passive"))
      (node (ref "C24") (pin "2") (pinfunction "2_2") (pintype "passive"))
      (node (ref "C25") (pin "-") (pinfunction "-_-") (pintype "passive"))
      (node (ref "C27") (pin "2") (pinfunction "2_2") (pintype "passive"))
      (node (ref "C29") (pin "2") (pinfunction "2_2") (pintype "passive"))
      (node (ref "C4") (pin "1") (pinfunction "1_1") (pintype "passive"))
      (node (ref "C5") (pin "1") (pinfunction "1_1") (pintype "passive"))
      (node (ref "C6") (pin "-") (pinfunction "-_-") (pintype "passive"))
      (node (ref "C7") (pin "1") (pinfunction "1_1") (pintype "passive"))
      (node (ref "C8") (pin "1") (pinfunction "1_1") (pintype "passive"))
      (node (ref "GPS") (pin "GND1") (pinfunction "GND1_GND1") (pintype "bidirectional"))
      (node (ref "GPS") (pin "GND2") (pinfunction "GND2_GND2") (pintype "bidirectional"))
      (node (ref "GPS") (pin "GND3") (pinfunction "GND3_GND3") (pintype "bidirectional"))
      (node (ref "GSM") (pin "GND1") (pinfunction "GND1_GND1") (pintype "bidirectional"))
      (node (ref "GSM") (pin "GND2") (pinfunction "GND2_GND2") (pintype "bidirectional"))
      (node (ref "GSM") (pin "GND3") (pinfunction "GND3_GND3") (pintype "bidirectional"))
      (node (ref "ICSP") (pin "4") (pinfunction "4_4") (pintype "bidirectional"))
      (node (ref "J1") (pin "7") (pinfunction "7_7") (pintype "bidirectional"))
      (node (ref "J14") (pin "-") (pinfunction "-_-") (pintype "bidirectional"))
      (node (ref "J2") (pin "5") (pinfunction "GND_5") (pintype "bidirectional"))
      (node (ref "J2") (pin "GND@1") (pinfunction "GND_GND@1") (pintype "bidirectional"))
      (node (ref "J2") (pin "GND@2") (pinfunction "GND_GND@2") (pintype "bidirectional"))
      (node (ref "J2") (pin "GND@3") (pinfunction "GND_GND@3") (pintype "bidirectional"))
      (node (ref "J2") (pin "GND@4") (pinfunction "GND_GND@4") (pintype "bidirectional"))
      (node (ref "J3") (pin "2") (pinfunction "2_2") (pintype "bidirectional"))
      (node (ref "J6") (pin "-") (pinfunction "-_-") (pintype "bidirectional"))
      (node (ref "J6") (pin "CDN") (pinfunction "CDN_CDN") (pintype "bidirectional"))
      (node (ref "J8") (pin "1") (pinfunction "1_1") (pintype "passive"))
      (node (ref "KEY") (pin "1") (pinfunction "1_1") (pintype "passive"))
      (node (ref "L") (pin "-") (pinfunction "-_-") (pintype "passive"))
      (node (ref "NET") (pin "-") (pinfunction "-_-") (pintype "passive"))
      (node (ref "POWER") (pin "2") (pinfunction "2_2") (pintype "bidirectional"))
      (node (ref "POWER") (pin "3") (pinfunction "3_3") (pintype "bidirectional"))
      (node (ref "PWR") (pin "-") (pinfunction "-_-") (pintype "passive"))
      (node (ref "Q2") (pin "2") (pinfunction "E_2") (pintype "passive"))
      (node (ref "R20") (pin "1") (pinfunction "1_1") (pintype "passive"))
      (node (ref "R23") (pin "1") (pinfunction "1_1") (pintype "passive"))
      (node (ref "R24") (pin "1") (pinfunction "1_1") (pintype "passive"))
      (node (ref "R7") (pin "2") (pinfunction "2_2") (pintype "passive"))
      (node (ref "RST") (pin "P$1") (pinfunction "1_P$1") (pintype "bidirectional"))
      (node (ref "STA") (pin "-") (pinfunction "-_-") (pintype "passive"))
      (node (ref "U1") (pin "21") (pinfunction "GND_21") (pintype "bidirectional"))
      (node (ref "U1") (pin "3") (pinfunction "GND_3") (pintype "bidirectional"))
      (node (ref "U1") (pin "5") (pinfunction "GND_5") (pintype "bidirectional"))
      (node (ref "U2") (pin "1") (pinfunction "TEMP_1") (pintype "input"))
      (node (ref "U2") (pin "3") (pinfunction "GND_3") (pintype "power_in"))
      (node (ref "U2") (pin "HEAT") (pinfunction "H_HEAT") (pintype "bidirectional"))
      (node (ref "U3") (pin "2") (pinfunction "GND_2") (pintype "bidirectional"))
      (node (ref "U5") (pin "18") (pinfunction "GND_18") (pintype "input"))
      (node (ref "U5") (pin "21") (pinfunction "GND_21") (pintype "input"))
      (node (ref "U5") (pin "25") (pinfunction "GND_25") (pintype "input"))
      (node (ref "U5") (pin "26") (pinfunction "TEST_26") (pintype "input"))
      (node (ref "U5") (pin "7") (pinfunction "GND_7") (pintype "input"))
      (node (ref "U6") (pin "1") (pinfunction "GND_1") (pintype "power_in"))
      (node (ref "U6") (pin "18") (pinfunction "GND_18") (pintype "input"))
      (node (ref "U6") (pin "2") (pinfunction "GND_2") (pintype "power_in"))
      (node (ref "U6") (pin "20") (pinfunction "MICIN_20") (pintype "output"))
      (node (ref "U6") (pin "28") (pinfunction "GND_28") (pintype "input"))
      (node (ref "U6") (pin "3") (pinfunction "GND_3") (pintype "output"))
      (node (ref "U6") (pin "34") (pinfunction "GND_34") (pintype "bidirectional"))
      (node (ref "U6") (pin "36") (pinfunction "GND_36") (pintype "output"))
      (node (ref "U6") (pin "40") (pinfunction "GND_40") (pintype "output"))
      (node (ref "U6") (pin "51") (pinfunction "GND_51") (pintype "bidirectional"))
      (node (ref "U6") (pin "52") (pinfunction "GND_52") (pintype "output"))
      (node (ref "U6") (pin "54") (pinfunction "GND_54") (pintype "power_in"))
      (node (ref "U6") (pin "64") (pinfunction "GND_64") (pintype "power_in"))
      (node (ref "U6") (pin "65") (pinfunction "GND_65") (pintype "power_in"))
      (node (ref "U6") (pin "67") (pinfunction "GND_67") (pintype "power_in"))
      (node (ref "U6") (pin "68") (pinfunction "GND_68") (pintype "power_in"))
      (node (ref "U7") (pin "7") (pinfunction "GND_7") (pintype "bidirectional"))
      (node (ref "U8") (pin "5") (pinfunction "GND_5") (pintype "bidirectional"))
      (node (ref "U9") (pin "1") (pinfunction "GND_1") (pintype "bidirectional"))
      (node (ref "Y2") (pin "2") (pinfunction "2_2") (pintype "passive"))
    )
    (net (code "82") (name "Net-(C2-Pad1)") (class "Default")
      (node (ref "C2") (pin "1") (pinfunction "1_1") (pintype "bidirectional"))
      (node (ref "R25") (pin "1") (pinfunction "1_1") (pintype "passive"))
    )
    (net (code "83") (name "Net-(C22-Pad2)") (class "Default")
      (node (ref "C22") (pin "2") (pinfunction "2_2") (pintype "passive"))
      (node (ref "J3") (pin "1") (pinfunction "1_1") (pintype "bidirectional"))
      (node (ref "R12") (pin "2") (pinfunction "2_2") (pintype "passive"))
    )
    (net (code "84") (name "Net-(C23-Pad2)") (class "Default")
      (node (ref "C23") (pin "2") (pinfunction "2_2") (pintype "passive"))
      (node (ref "L1") (pin "1") (pinfunction "1_1") (pintype "passive"))
      (node (ref "R8") (pin "2") (pinfunction "2_2") (pintype "passive"))
    )
    (net (code "85") (name "Net-(CH-Pad+)") (class "Default")
      (node (ref "CH") (pin "+") (pinfunction "+_+") (pintype "passive"))
      (node (ref "R21") (pin "1") (pinfunction "1_1") (pintype "passive"))
    )
    (net (code "86") (name "Net-(J2-VCC)") (class "Default")
      (node (ref "F2") (pin "1") (pinfunction "1_1") (pintype "bidirectional"))
      (node (ref "J2") (pin "1") (pinfunction "VCC_1") (pintype "bidirectional"))
    )
    (net (code "87") (name "Net-(L-Pad+)") (class "Default")
      (node (ref "L") (pin "+") (pinfunction "+_+") (pintype "passive"))
      (node (ref "R3") (pin "2") (pinfunction "2_2") (pintype "passive"))
    )
    (net (code "88") (name "Net-(NET-Pad+)") (class "Default")
      (node (ref "NET") (pin "+") (pinfunction "+_+") (pintype "passive"))
      (node (ref "R4") (pin "2") (pinfunction "2_2") (pintype "passive"))
    )
    (net (code "89") (name "Net-(OK-Pad+)") (class "Default")
      (node (ref "OK") (pin "+") (pinfunction "+_+") (pintype "passive"))
      (node (ref "R26") (pin "1") (pinfunction "1_1") (pintype "passive"))
    )
    (net (code "90") (name "Net-(PWR-Pad+)") (class "Default")
      (node (ref "PWR") (pin "+") (pinfunction "+_+") (pintype "passive"))
      (node (ref "R10") (pin "2") (pinfunction "2_2") (pintype "passive"))
    )
    (net (code "91") (name "Net-(Q2-B)") (class "Default")
      (node (ref "Q2") (pin "1") (pinfunction "B_1") (pintype "passive"))
      (node (ref "R22") (pin "2") (pinfunction "2_2") (pintype "passive"))
      (node (ref "R23") (pin "2") (pinfunction "2_2") (pintype "passive"))
    )
    (net (code "92") (name "Net-(R5-Pad2)") (class "Default")
      (node (ref "R5") (pin "2") (pinfunction "2_2") (pintype "passive"))
      (node (ref "STA") (pin "+") (pinfunction "+_+") (pintype "passive"))
    )
    (net (code "93") (name "Net-(R13-Pad2)") (class "Default")
      (node (ref "R13") (pin "2") (pinfunction "2_2") (pintype "passive"))
      (node (ref "RX") (pin "+") (pinfunction "+_+") (pintype "passive"))
    )
    (net (code "94") (name "Net-(R14-Pad2)") (class "Default")
      (node (ref "R14") (pin "2") (pinfunction "2_2") (pintype "passive"))
      (node (ref "TX") (pin "+") (pinfunction "+_+") (pintype "passive"))
    )
    (net (code "95") (name "Net-(U2-CHRG)") (class "Default")
      (node (ref "CH") (pin "-") (pinfunction "-_-") (pintype "passive"))
      (node (ref "U2") (pin "7") (pinfunction "CHRG_7") (pintype "bidirectional"))
    )
    (net (code "96") (name "Net-(U2-DONE)") (class "Default")
      (node (ref "OK") (pin "-") (pinfunction "-_-") (pintype "passive"))
      (node (ref "U2") (pin "6") (pinfunction "DONE_6") (pintype "bidirectional"))
    )
    (net (code "97") (name "Net-(U2-ISET)") (class "Default")
      (node (ref "R20") (pin "2") (pinfunction "2_2") (pintype "passive"))
      (node (ref "U2") (pin "2") (pinfunction "ISET_2") (pintype "bidirectional"))
    )
    (net (code "98") (name "Net-(U3-SW)") (class "Default")
      (node (ref "C3") (pin "1") (pinfunction "1_1") (pintype "passive"))
      (node (ref "L2") (pin "2") (pinfunction "2_2") (pintype "passive"))
      (node (ref "U3") (pin "5") (pinfunction "SW_5") (pintype "bidirectional"))
    )
    (net (code "99") (name "Net-(U4-ADJ)") (class "Default")
      (node (ref "R7") (pin "1") (pinfunction "1_1") (pintype "passive"))
      (node (ref "R9") (pin "2") (pinfunction "2_2") (pintype "passive"))
      (node (ref "U4") (pin "1") (pinfunction "ADJ_1") (pintype "bidirectional"))
    )
    (net (code "100") (name "Net-(U5-3V3OUT)") (class "Default")
      (node (ref "C8") (pin "2") (pinfunction "2_2") (pintype "passive"))
      (node (ref "U5") (pin "17") (pinfunction "3V3OUT_17") (pintype "input"))
      (node (ref "U5") (pin "19") (pinfunction "~{RESET}_19") (pintype "input"))
    )
    (net (code "101") (name "Net-(U6-MICIP)") (class "Default")
      (node (ref "C21") (pin "1") (pinfunction "1_1") (pintype "passive"))
      (node (ref "R12") (pin "1") (pinfunction "1_1") (pintype "passive"))
      (node (ref "U6") (pin "19") (pinfunction "MICIP_19") (pintype "input"))
    )
    (net (code "102") (name "Net-(U6-RESET)") (class "Default")
      (node (ref "D2") (pin "+") (pinfunction "+_+") (pintype "passive"))
      (node (ref "U6") (pin "16") (pinfunction "RESET_16") (pintype "input"))
    )
    (net (code "103") (name "Net-(U6-SPKIN)") (class "Default")
      (node (ref "C15") (pin "2") (pinfunction "2_2") (pintype "passive"))
      (node (ref "C16") (pin "1") (pinfunction "1_1") (pintype "passive"))
      (node (ref "C19") (pin "2") (pinfunction "2_2") (pintype "passive"))
      (node (ref "C20") (pin "1") (pinfunction "1_1") (pintype "passive"))
      (node (ref "J3") (pin "3") (pinfunction "3_3") (pintype "bidirectional"))
      (node (ref "U6") (pin "22") (pinfunction "SPKIN_22") (pintype "bidirectional"))
    )
    (net (code "104") (name "Net-(U6-SPKIP)") (class "Default")
      (node (ref "C16") (pin "2") (pinfunction "2_2") (pintype "passive"))
      (node (ref "C17") (pin "1") (pinfunction "1_1") (pintype "passive"))
      (node (ref "C18") (pin "1") (pinfunction "1_1") (pintype "passive"))
      (node (ref "C20") (pin "2") (pinfunction "2_2") (pintype "passive"))
      (node (ref "J3") (pin "4") (pinfunction "4_4") (pintype "bidirectional"))
      (node (ref "U6") (pin "21") (pinfunction "SPKIP_21") (pintype "output"))
    )
    (net (code "105") (name "Net-(U8-CLK)") (class "Default")
      (node (ref "R18") (pin "1") (pinfunction "1_1") (pintype "passive"))
      (node (ref "U8") (pin "3") (pinfunction "CLK_3") (pintype "bidirectional"))
    )
    (net (code "106") (name "Net-(U8-I{slash}O)") (class "Default")
      (node (ref "R19") (pin "2") (pinfunction "2_2") (pintype "passive"))
      (node (ref "U8") (pin "7") (pinfunction "I/O_7") (pintype "bidirectional"))
    )
    (net (code "107") (name "Net-(U8-RST)") (class "Default")
      (node (ref "R17") (pin "1") (pinfunction "1_1") (pintype "passive"))
      (node (ref "U8") (pin "2") (pinfunction "RST_2") (pintype "bidirectional"))
    )
    (net (code "108") (name "Net-(U10B--IN2)") (class "Default")
      (node (ref "R3") (pin "1") (pinfunction "1_1") (pintype "passive"))
      (node (ref "U10") (pin "6") (pinfunction "-IN2_6") (pintype "input"))
      (node (ref "U10") (pin "7") (pinfunction "OUT2_7") (pintype "output"))
    )
    (net (code "109") (name "VIN") (class "Default")
      (node (ref "C1") (pin "+") (pinfunction "+_+") (pintype "passive"))
      (node (ref "C27") (pin "1") (pinfunction "1_1") (pintype "passive"))
      (node (ref "J6") (pin "+") (pinfunction "+_+") (pintype "bidirectional"))
      (node (ref "L2") (pin "1") (pinfunction "1_1") (pintype "passive"))
      (node (ref "Q3") (pin "1") (pinfunction "G_1") (pintype "passive"))
      (node (ref "Q3") (pin "3") (pinfunction "D_3") (pintype "passive"))
      (node (ref "R21") (pin "2") (pinfunction "2_2") (pintype "passive"))
      (node (ref "R24") (pin "2") (pinfunction "2_2") (pintype "passive"))
      (node (ref "R26") (pin "2") (pinfunction "2_2") (pintype "passive"))
      (node (ref "U2") (pin "4") (pinfunction "VIN_4") (pintype "input"))
      (node (ref "U3") (pin "3") (pinfunction "EN_3") (pintype "bidirectional"))
      (node (ref "U3") (pin "4") (pinfunction "IN_4") (pintype "bidirectional"))
    )
    (net (code "110") (name "unconnected-(J2-ID-Pad4)") (class "Default")
      (node (ref "J2") (pin "4") (pinfunction "ID_4") (pintype "bidirectional"))
    )
    (net (code "111") (name "unconnected-(J3-Pad5)") (class "Default")
      (node (ref "J3") (pin "5") (pinfunction "5_5") (pintype "bidirectional"))
    )
    (net (code "112") (name "unconnected-(J3-Pad6)") (class "Default")
      (node (ref "J3") (pin "6") (pinfunction "6_6") (pintype "bidirectional"))
    )
    (net (code "113") (name "unconnected-(J3-Pad7)") (class "Default")
      (node (ref "J3") (pin "7") (pinfunction "7_7") (pintype "bidirectional"))
    )
    (net (code "114") (name "unconnected-(J3-Pad8)") (class "Default")
      (node (ref "J3") (pin "8") (pinfunction "8_8") (pintype "bidirectional"))
    )
    (net (code "115") (name "unconnected-(POWER-Pad8)") (class "Default")
      (node (ref "POWER") (pin "8") (pinfunction "8_8") (pintype "bidirectional"))
    )
    (net (code "116") (name "unconnected-(U5-CBUS2-Pad13)") (class "Default")
      (node (ref "U5") (pin "13") (pinfunction "CBUS2_13") (pintype "input"))
    )
    (net (code "117") (name "unconnected-(U5-CBUS3-Pad14)") (class "Default")
      (node (ref "U5") (pin "14") (pinfunction "CBUS3_14") (pintype "input"))
    )
    (net (code "118") (name "unconnected-(U5-CBUS4-Pad12)") (class "Default")
      (node (ref "U5") (pin "12") (pinfunction "CBUS4_12") (pintype "input"))
    )
    (net (code "119") (name "unconnected-(U5-OSCI-Pad27)") (class "Default")
      (node (ref "U5") (pin "27") (pinfunction "OSCI_27") (pintype "input"))
    )
    (net (code "120") (name "unconnected-(U5-OSCO-Pad28)") (class "Default")
      (node (ref "U5") (pin "28") (pinfunction "OSCO_28") (pintype "input"))
    )
    (net (code "121") (name "unconnected-(U6-CTS-Pad12)") (class "Default")
      (node (ref "U6") (pin "12") (pinfunction "CTS_12") (pintype "output"))
    )
    (net (code "122") (name "unconnected-(U6-DCD-Pad11)") (class "Default")
      (node (ref "U6") (pin "11") (pinfunction "DCD_11") (pintype "output"))
    )
    (net (code "123") (name "unconnected-(U6-DTR-Pad9)") (class "Default")
      (node (ref "U6") (pin "9") (pinfunction "DTR_9") (pintype "input"))
    )
    (net (code "124") (name "unconnected-(U6-PCM_CLK-Pad46)") (class "Default")
      (node (ref "U6") (pin "46") (pinfunction "PCM_CLK_46") (pintype "bidirectional"))
    )
    (net (code "125") (name "unconnected-(U6-PCM_IN-Pad47)") (class "Default")
      (node (ref "U6") (pin "47") (pinfunction "PCM_IN_47") (pintype "input"))
    )
    (net (code "126") (name "unconnected-(U6-PCM_OUT-Pad48)") (class "Default")
      (node (ref "U6") (pin "48") (pinfunction "PCM_OUT_48") (pintype "input"))
    )
    (net (code "127") (name "unconnected-(U6-PCM_SYNC-Pad45)") (class "Default")
      (node (ref "U6") (pin "45") (pinfunction "PCM_SYNC_45") (pintype "input"))
    )
    (net (code "128") (name "unconnected-(U6-RI-Pad10)") (class "Default")
      (node (ref "U6") (pin "10") (pinfunction "RI_10") (pintype "output"))
    )
    (net (code "129") (name "unconnected-(U6-RTS-Pad13)") (class "Default")
      (node (ref "U6") (pin "13") (pinfunction "RTS_13") (pintype "input"))
    )
    (net (code "130") (name "unconnected-(U6-SIM_PRE-Pad33)") (class "Default")
      (node (ref "U6") (pin "33") (pinfunction "SIM_PRE_33") (pintype "bidirectional"))
    )
    (net (code "131") (name "unconnected-(U6-USB_DM-Pad27)") (class "Default")
      (node (ref "U6") (pin "27") (pinfunction "USB_DM_27") (pintype "bidirectional"))
    )
    (net (code "132") (name "unconnected-(U6-USB_DP-Pad26)") (class "Default")
      (node (ref "U6") (pin "26") (pinfunction "USB_DP_26") (pintype "input"))
    )
    (net (code "133") (name "unconnected-(U6-VBUS-Pad25)") (class "Default")
      (node (ref "U6") (pin "25") (pinfunction "VBUS_25") (pintype "output"))
    )
    (net (code "134") (name "unconnected-(U8-VPP-Pad6)") (class "Default")
      (node (ref "U8") (pin "6") (pinfunction "VPP_6") (pintype "bidirectional"))
    )
  )
)
